# brick_analog_led_red.net
KiCad netlist of a schematic drawn in EAGLE
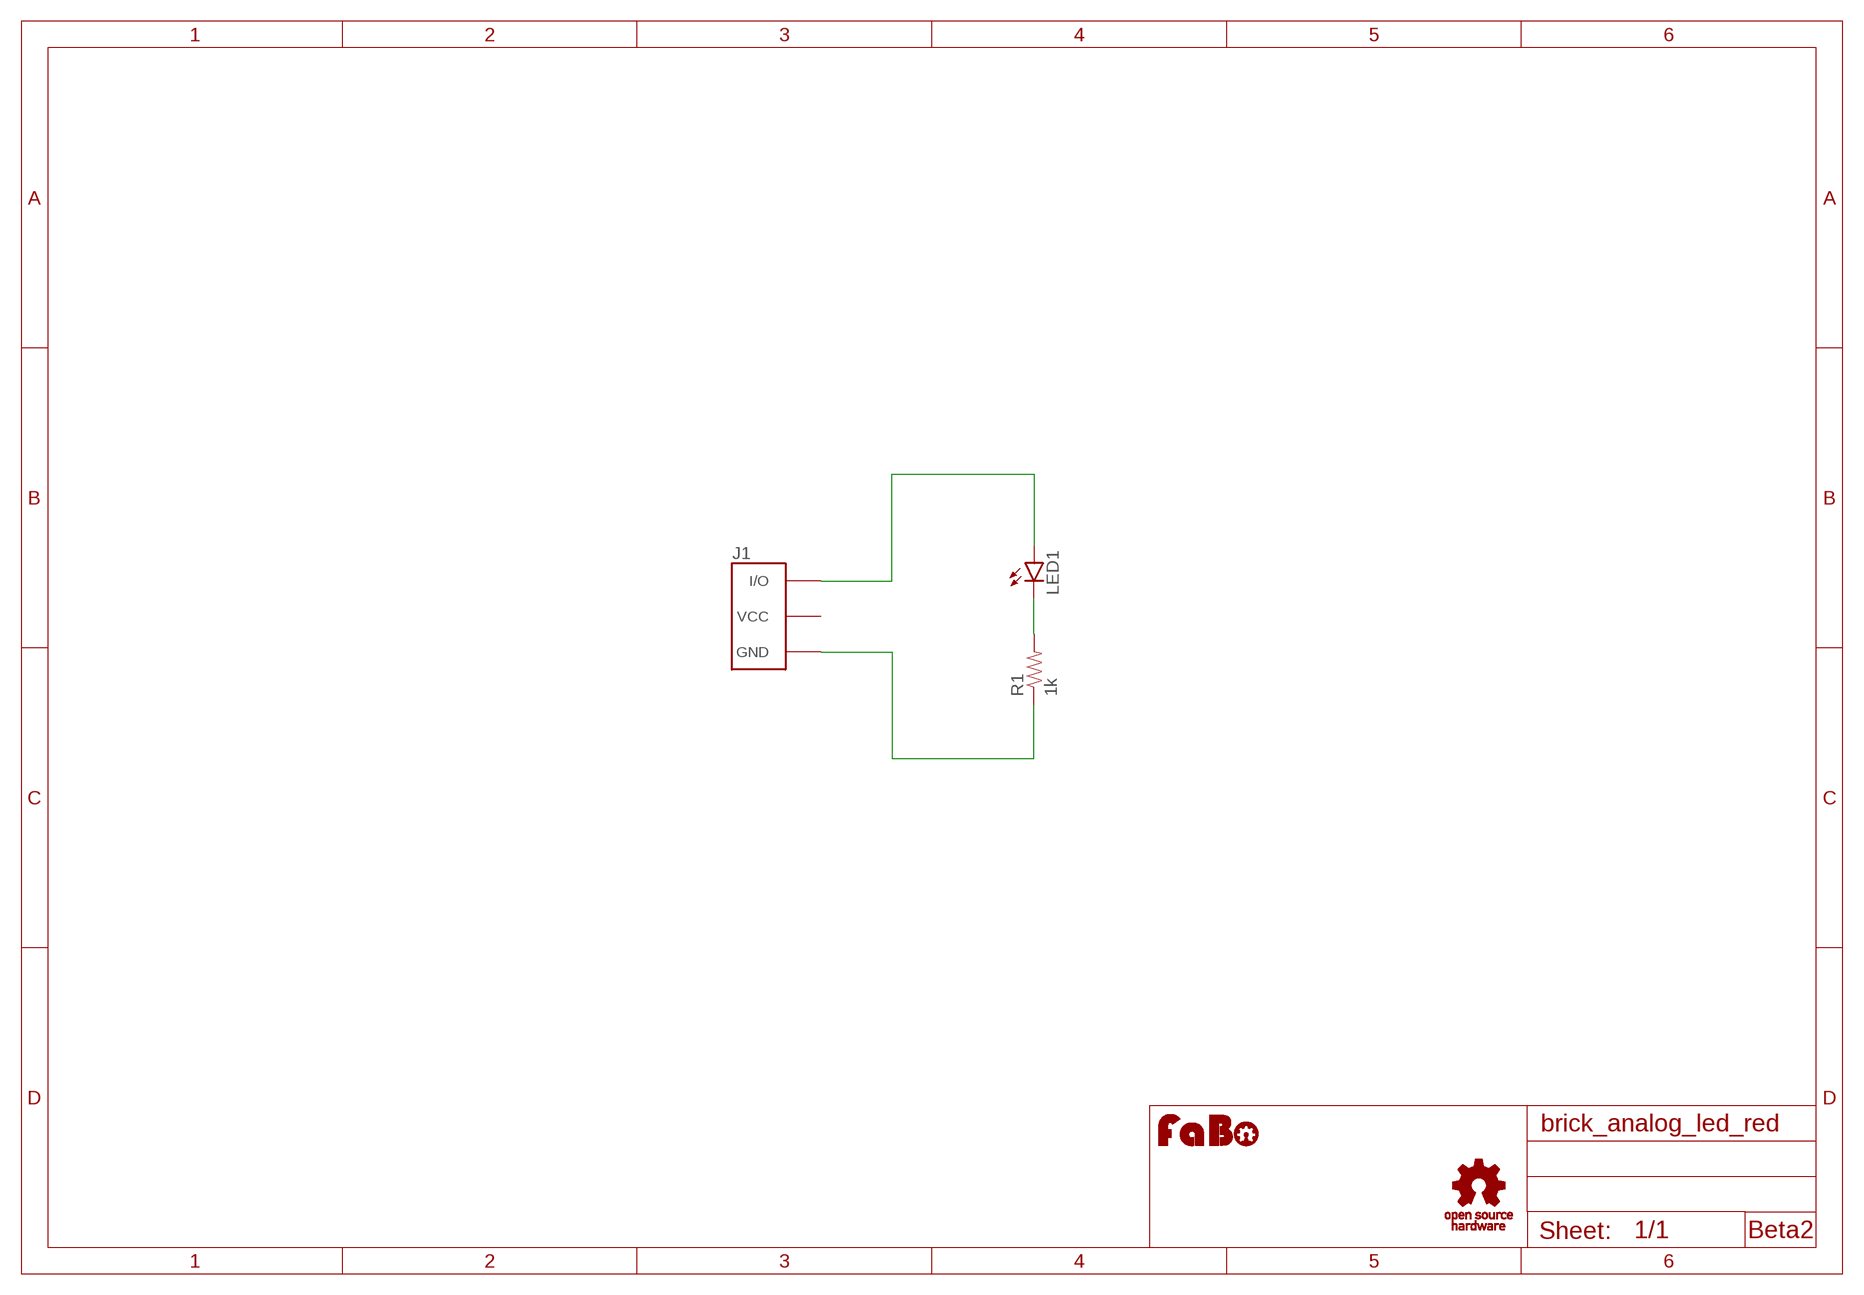
[diagram p0: schematic, sheet 1]

(export (version "E")
  (design (tool "Eeschema 10.0.6"))
  (components
    (comp (ref "J1")
      (value "BRICK_3PIN")
      (footprint "eagle-import:BRICK_3PIN")
      (libsource (lib "eagle-import") (part "BRICK_3PIN"))
    )
    (comp (ref "LED1")
      (value "LED-5MM")
      (footprint "eagle-import:LED-5MM")
      (libsource (lib "eagle-import") (part "LED-5MM"))
    )
    (comp (ref "R1")
      (value "1k")
      (footprint "eagle-import:RES-AXL-REGULAR")
      (libsource (lib "eagle-import") (part "RES-PTH-REGULAR"))
    )
    (comp (ref "U$1")
      (value "LOGO_FABO-M")
      (footprint "eagle-import:LOGO_FABO_M")
      (libsource (lib "eagle-import") (part "LOGO_FABO-M"))
    )
    (comp (ref "U$4")
      (value "LOGO_OSHW_T-M")
      (footprint "eagle-import:LOGO_OSHW_T_M")
      (libsource (lib "eagle-import") (part "LOGO_OSHW_T-M"))
    )
  )
  (nets
    (net (code "1") (name "Net-(J1-I{slash}O)") (class "Default")
      (node (ref "J1") (pin "IN/OUT") (pinfunction "I/O_IN/OUT") (pintype "bidirectional"))
      (node (ref "LED1") (pin "A") (pinfunction "A_A") (pintype "passive"))
    )
    (net (code "2") (name "Net-(LED1-C)") (class "Default")
      (node (ref "LED1") (pin "K") (pinfunction "C_K") (pintype "passive"))
      (node (ref "R1") (pin "P$2") (pinfunction "2_P$2") (pintype "passive"))
    )
    (net (code "3") (name "Net-(R1-1)") (class "Default")
      (node (ref "J1") (pin "GND") (pinfunction "GND_GND") (pintype "bidirectional"))
      (node (ref "R1") (pin "P$1") (pinfunction "1_P$1") (pintype "passive"))
    )
    (net (code "4") (name "unconnected-(J1-PadVCC)") (class "Default")
      (node (ref "J1") (pin "VCC") (pinfunction "VCC_VCC") (pintype "bidirectional"))
    )
  )
)
